# Analog_-_High_Speed_SE.net
KiCad netlist of a schematic drawn in Altium Designer
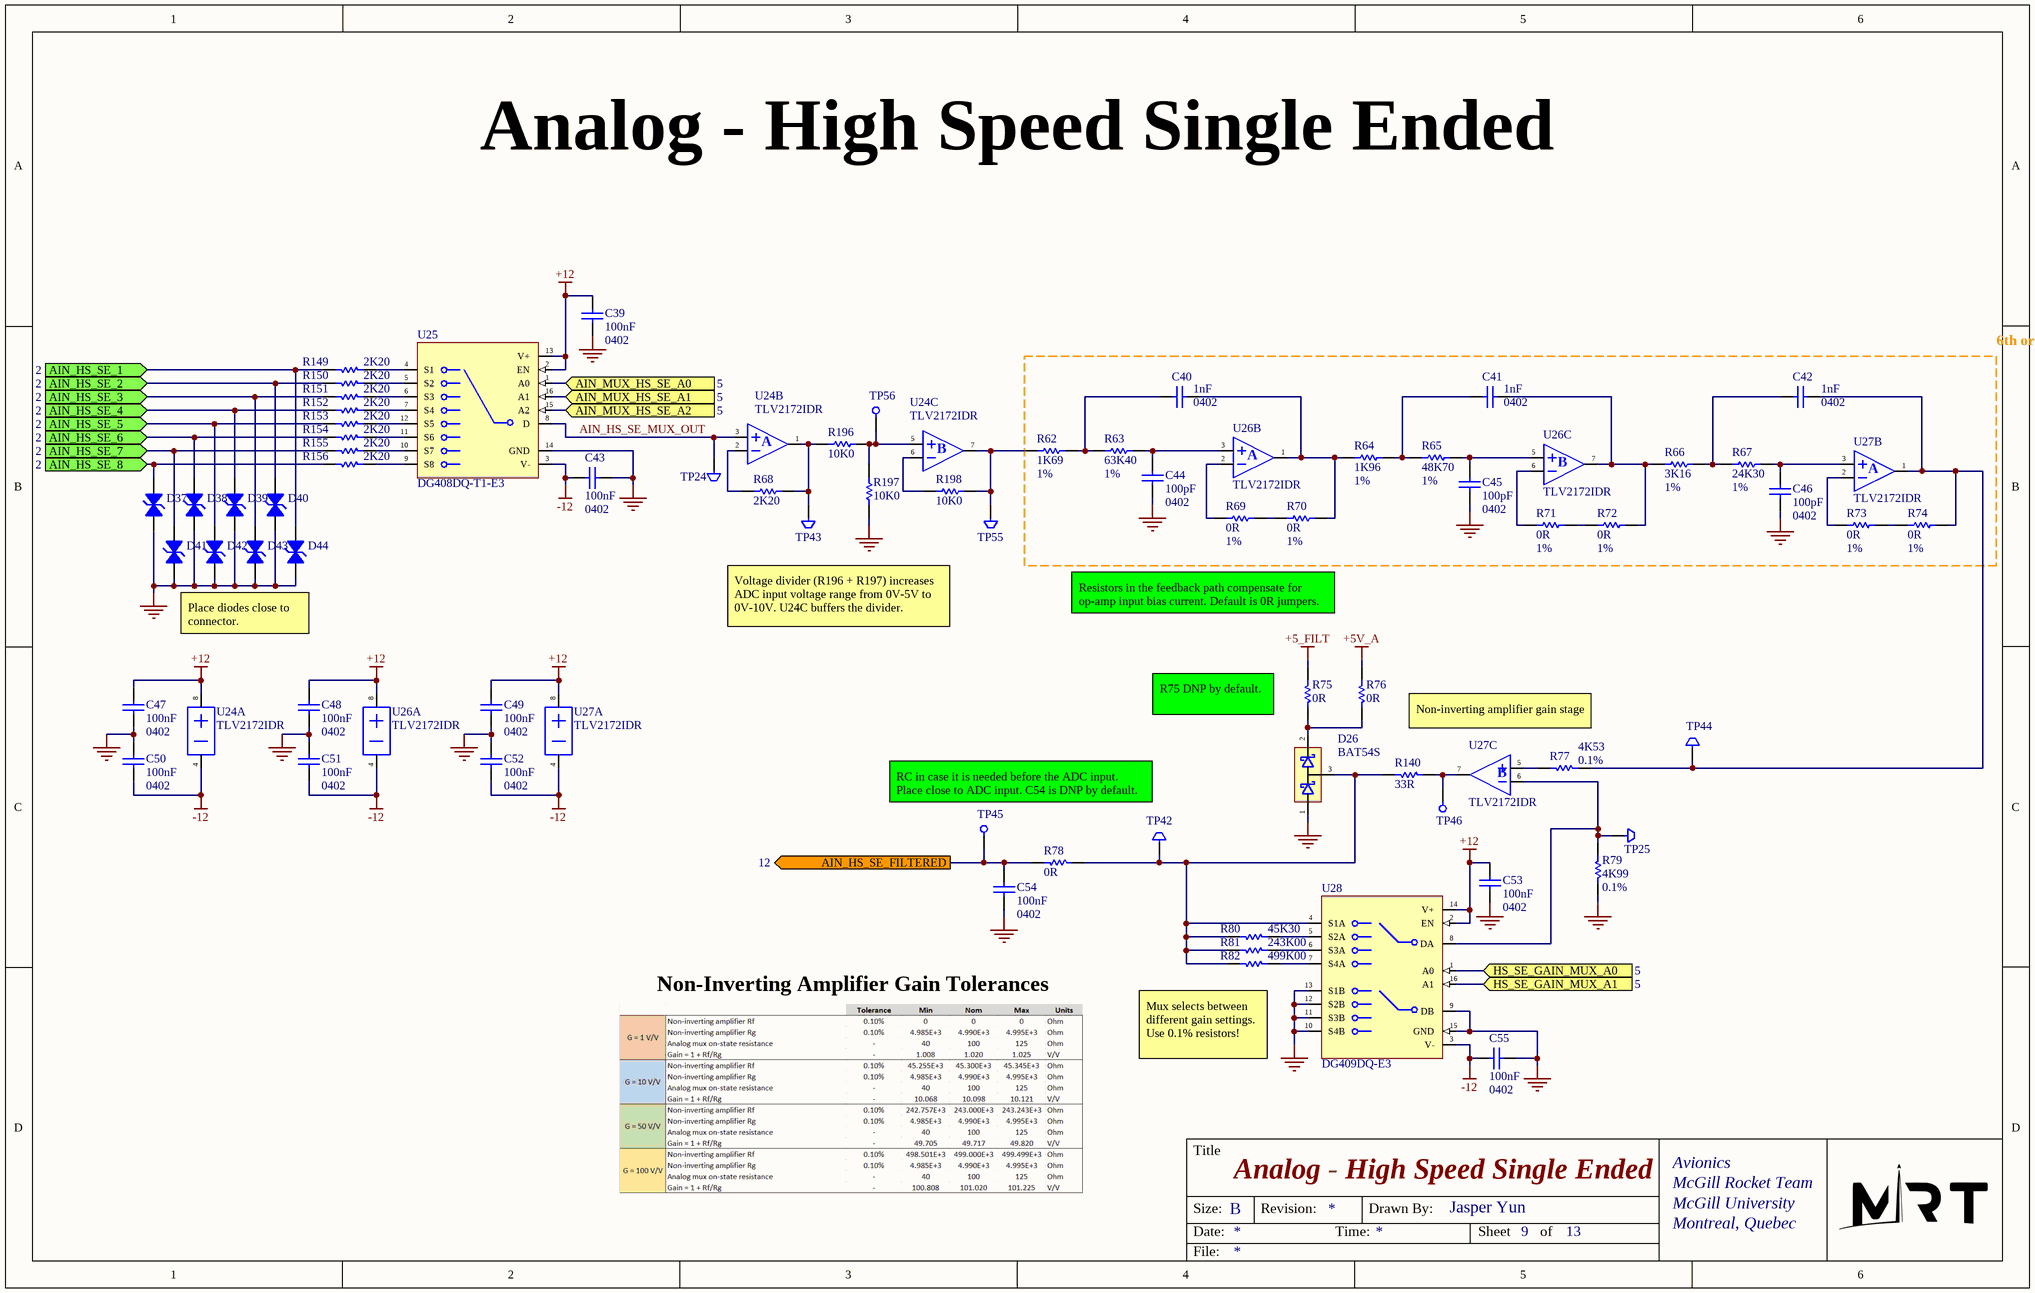
[diagram p0: Analog - High Speed SE.SchDoc]

(export (version "E")
  (design (tool "Eeschema 10.0.6"))
  (components
    (comp (ref "C39")
      (value "100nF")
      (footprint "0402 CAP")
      (description "Capacitor")
      (fields (field (name "ALTIUM_VALUE") "0402") (field (name "PUBLISHER") "Altium Limited"))
      (libsource (lib "Miscellaneous Devices") (part "Cap"))
    )
    (comp (ref "C40")
      (value "1nF")
      (footprint "0402 CAP")
      (description "Capacitor")
      (fields (field (name "ALTIUM_VALUE") "0402") (field (name "PUBLISHER") "Altium Limited"))
      (libsource (lib "Miscellaneous Devices") (part "Cap"))
    )
    (comp (ref "C41")
      (value "1nF")
      (footprint "0402 CAP")
      (description "Capacitor")
      (fields (field (name "ALTIUM_VALUE") "0402") (field (name "PUBLISHER") "Altium Limited"))
      (libsource (lib "Miscellaneous Devices") (part "Cap"))
    )
    (comp (ref "C42")
      (value "1nF")
      (footprint "0402 CAP")
      (description "Capacitor")
      (fields (field (name "ALTIUM_VALUE") "0402") (field (name "PUBLISHER") "Altium Limited"))
      (libsource (lib "Miscellaneous Devices") (part "Cap"))
    )
    (comp (ref "C43")
      (value "100nF")
      (footprint "0402 CAP")
      (description "Capacitor")
      (fields (field (name "ALTIUM_VALUE") "0402") (field (name "PUBLISHER") "Altium Limited"))
      (libsource (lib "Miscellaneous Devices") (part "Cap"))
    )
    (comp (ref "C44")
      (value "100pF")
      (footprint "0402 CAP")
      (description "Capacitor")
      (fields (field (name "ALTIUM_VALUE") "0402") (field (name "PUBLISHER") "Altium Limited"))
      (libsource (lib "Miscellaneous Devices") (part "Cap"))
    )
    (comp (ref "C45")
      (value "100pF")
      (footprint "0402 CAP")
      (description "Capacitor")
      (fields (field (name "ALTIUM_VALUE") "0402") (field (name "PUBLISHER") "Altium Limited"))
      (libsource (lib "Miscellaneous Devices") (part "Cap"))
    )
    (comp (ref "C46")
      (value "100pF")
      (footprint "0402 CAP")
      (description "Capacitor")
      (fields (field (name "ALTIUM_VALUE") "0402") (field (name "PUBLISHER") "Altium Limited"))
      (libsource (lib "Miscellaneous Devices") (part "Cap"))
    )
    (comp (ref "C47")
      (value "100nF")
      (footprint "0402 CAP")
      (description "Capacitor")
      (fields (field (name "ALTIUM_VALUE") "0402") (field (name "PUBLISHER") "Altium Limited"))
      (libsource (lib "Miscellaneous Devices") (part "Cap"))
    )
    (comp (ref "C48")
      (value "100nF")
      (footprint "0402 CAP")
      (description "Capacitor")
      (fields (field (name "ALTIUM_VALUE") "0402") (field (name "PUBLISHER") "Altium Limited"))
      (libsource (lib "Miscellaneous Devices") (part "Cap"))
    )
    (comp (ref "C49")
      (value "100nF")
      (footprint "0402 CAP")
      (description "Capacitor")
      (fields (field (name "ALTIUM_VALUE") "0402") (field (name "PUBLISHER") "Altium Limited"))
      (libsource (lib "Miscellaneous Devices") (part "Cap"))
    )
    (comp (ref "C50")
      (value "100nF")
      (footprint "0402 CAP")
      (description "Capacitor")
      (fields (field (name "ALTIUM_VALUE") "0402") (field (name "PUBLISHER") "Altium Limited"))
      (libsource (lib "Miscellaneous Devices") (part "Cap"))
    )
    (comp (ref "C51")
      (value "100nF")
      (footprint "0402 CAP")
      (description "Capacitor")
      (fields (field (name "ALTIUM_VALUE") "0402") (field (name "PUBLISHER") "Altium Limited"))
      (libsource (lib "Miscellaneous Devices") (part "Cap"))
    )
    (comp (ref "C52")
      (value "100nF")
      (footprint "0402 CAP")
      (description "Capacitor")
      (fields (field (name "ALTIUM_VALUE") "0402") (field (name "PUBLISHER") "Altium Limited"))
      (libsource (lib "Miscellaneous Devices") (part "Cap"))
    )
    (comp (ref "C53")
      (value "100nF")
      (footprint "0402 CAP")
      (description "Capacitor")
      (fields (field (name "ALTIUM_VALUE") "0402") (field (name "PUBLISHER") "Altium Limited"))
      (libsource (lib "Miscellaneous Devices") (part "Cap"))
    )
    (comp (ref "C54")
      (value "100nF")
      (footprint "0402 CAP")
      (description "Capacitor")
      (fields (field (name "ALTIUM_VALUE") "0402") (field (name "PUBLISHER") "Altium Limited"))
      (libsource (lib "Miscellaneous Devices") (part "Cap"))
    )
    (comp (ref "C55")
      (value "100nF")
      (footprint "0402 CAP")
      (description "Capacitor")
      (fields (field (name "ALTIUM_VALUE") "0402") (field (name "PUBLISHER") "Altium Limited"))
      (libsource (lib "Miscellaneous Devices") (part "Cap"))
    )
    (comp (ref "D26")
      (value "BAT54S")
      (footprint "SOT23-3")
      (description "Rectifier Diode Small Signal Schottky 40V 0.3A 5ns 3-Pin SOT-23 T/R")
      (fields
        (field (name "MANUFACTURER") "STMicroelectronics")
        (field (name "MANUFACTURER PART NUMBER") "BAT54SFILM")
      )
      (libsource (lib "MRT SCH Library") (part "Schottky Diode Array BAT54S"))
    )
    (comp (ref "D37")
      (value "D12V0L1B2LP-7B")
      (footprint "DFN1006-2")
      (description "Bidirectional Zener diode")
      (libsource (lib "MRT SCH Library") (part "Diode Zener Bidirectional"))
    )
    (comp (ref "D38")
      (value "D12V0L1B2LP-7B")
      (footprint "DFN1006-2")
      (description "Bidirectional Zener diode")
      (libsource (lib "MRT SCH Library") (part "Diode Zener Bidirectional"))
    )
    (comp (ref "D39")
      (value "D12V0L1B2LP-7B")
      (footprint "DFN1006-2")
      (description "Bidirectional Zener diode")
      (libsource (lib "MRT SCH Library") (part "Diode Zener Bidirectional"))
    )
    (comp (ref "D40")
      (value "D12V0L1B2LP-7B")
      (footprint "DFN1006-2")
      (description "Bidirectional Zener diode")
      (libsource (lib "MRT SCH Library") (part "Diode Zener Bidirectional"))
    )
    (comp (ref "D41")
      (value "D12V0L1B2LP-7B")
      (footprint "DFN1006-2")
      (description "Bidirectional Zener diode")
      (libsource (lib "MRT SCH Library") (part "Diode Zener Bidirectional"))
    )
    (comp (ref "D42")
      (value "D12V0L1B2LP-7B")
      (footprint "DFN1006-2")
      (description "Bidirectional Zener diode")
      (libsource (lib "MRT SCH Library") (part "Diode Zener Bidirectional"))
    )
    (comp (ref "D43")
      (value "D12V0L1B2LP-7B")
      (footprint "DFN1006-2")
      (description "Bidirectional Zener diode")
      (libsource (lib "MRT SCH Library") (part "Diode Zener Bidirectional"))
    )
    (comp (ref "D44")
      (value "D12V0L1B2LP-7B")
      (footprint "DFN1006-2")
      (description "Bidirectional Zener diode")
      (libsource (lib "MRT SCH Library") (part "Diode Zener Bidirectional"))
    )
    (comp (ref "R62")
      (value "1K69")
      (footprint "0402 RES")
      (description "Resistor")
      (fields (field (name "ALTIUM_VALUE") "1%") (field (name "PUBLISHER") "Altium Limited"))
      (libsource (lib "Miscellaneous Devices") (part "Res1"))
    )
    (comp (ref "R63")
      (value "63K40")
      (footprint "0402 RES")
      (description "Resistor")
      (fields (field (name "ALTIUM_VALUE") "1%") (field (name "PUBLISHER") "Altium Limited"))
      (libsource (lib "Miscellaneous Devices") (part "Res1"))
    )
    (comp (ref "R64")
      (value "1K96")
      (footprint "0402 RES")
      (description "Resistor")
      (fields (field (name "ALTIUM_VALUE") "1%") (field (name "PUBLISHER") "Altium Limited"))
      (libsource (lib "Miscellaneous Devices") (part "Res1"))
    )
    (comp (ref "R65")
      (value "48K70")
      (footprint "0402 RES")
      (description "Resistor")
      (fields (field (name "ALTIUM_VALUE") "1%") (field (name "PUBLISHER") "Altium Limited"))
      (libsource (lib "Miscellaneous Devices") (part "Res1"))
    )
    (comp (ref "R66")
      (value "3K16")
      (footprint "0402 RES")
      (description "Resistor")
      (fields (field (name "ALTIUM_VALUE") "1%") (field (name "PUBLISHER") "Altium Limited"))
      (libsource (lib "Miscellaneous Devices") (part "Res1"))
    )
    (comp (ref "R67")
      (value "24K30")
      (footprint "0402 RES")
      (description "Resistor")
      (fields (field (name "ALTIUM_VALUE") "1%") (field (name "PUBLISHER") "Altium Limited"))
      (libsource (lib "Miscellaneous Devices") (part "Res1"))
    )
    (comp (ref "R68")
      (value "2K20")
      (footprint "0402 RES")
      (description "Resistor")
      (fields (field (name "PUBLISHER") "Altium Limited"))
      (libsource (lib "Miscellaneous Devices") (part "Res1"))
    )
    (comp (ref "R69")
      (value "0R")
      (footprint "0402 RES")
      (description "Resistor")
      (fields (field (name "ALTIUM_VALUE") "1%") (field (name "PUBLISHER") "Altium Limited"))
      (libsource (lib "Miscellaneous Devices") (part "Res1"))
    )
    (comp (ref "R70")
      (value "0R")
      (footprint "0402 RES")
      (description "Resistor")
      (fields (field (name "ALTIUM_VALUE") "1%") (field (name "PUBLISHER") "Altium Limited"))
      (libsource (lib "Miscellaneous Devices") (part "Res1"))
    )
    (comp (ref "R71")
      (value "0R")
      (footprint "0402 RES")
      (description "Resistor")
      (fields (field (name "ALTIUM_VALUE") "1%") (field (name "PUBLISHER") "Altium Limited"))
      (libsource (lib "Miscellaneous Devices") (part "Res1"))
    )
    (comp (ref "R72")
      (value "0R")
      (footprint "0402 RES")
      (description "Resistor")
      (fields (field (name "ALTIUM_VALUE") "1%") (field (name "PUBLISHER") "Altium Limited"))
      (libsource (lib "Miscellaneous Devices") (part "Res1"))
    )
    (comp (ref "R73")
      (value "0R")
      (footprint "0402 RES")
      (description "Resistor")
      (fields (field (name "ALTIUM_VALUE") "1%") (field (name "PUBLISHER") "Altium Limited"))
      (libsource (lib "Miscellaneous Devices") (part "Res1"))
    )
    (comp (ref "R74")
      (value "0R")
      (footprint "0402 RES")
      (description "Resistor")
      (fields (field (name "ALTIUM_VALUE") "1%") (field (name "PUBLISHER") "Altium Limited"))
      (libsource (lib "Miscellaneous Devices") (part "Res1"))
    )
    (comp (ref "R75")
      (value "0R")
      (footprint "0402 RES")
      (description "Resistor")
      (fields (field (name "PUBLISHER") "Altium Limited"))
      (libsource (lib "Miscellaneous Devices") (part "Res1"))
    )
    (comp (ref "R76")
      (value "0R")
      (footprint "0402 RES")
      (description "Resistor")
      (fields (field (name "PUBLISHER") "Altium Limited"))
      (libsource (lib "Miscellaneous Devices") (part "Res1"))
    )
    (comp (ref "R77")
      (value "4K53")
      (footprint "0402 RES")
      (description "Resistor")
      (fields (field (name "ALTIUM_VALUE") "0.1%") (field (name "PUBLISHER") "Altium Limited"))
      (libsource (lib "Miscellaneous Devices") (part "Res1"))
    )
    (comp (ref "R78")
      (value "0R")
      (footprint "0402 RES")
      (description "Resistor")
      (fields (field (name "PUBLISHER") "Altium Limited"))
      (libsource (lib "Miscellaneous Devices") (part "Res1"))
    )
    (comp (ref "R79")
      (value "4K99")
      (footprint "0402 RES")
      (description "Resistor")
      (fields (field (name "ALTIUM_VALUE") "0.1%") (field (name "PUBLISHER") "Altium Limited"))
      (libsource (lib "Miscellaneous Devices") (part "Res1"))
    )
    (comp (ref "R80")
      (value "45K30")
      (footprint "0402 RES")
      (description "Resistor")
      (fields (field (name "PUBLISHER") "Altium Limited"))
      (libsource (lib "Miscellaneous Devices") (part "Res1"))
    )
    (comp (ref "R81")
      (value "243K00")
      (footprint "0402 RES")
      (description "Resistor")
      (fields (field (name "PUBLISHER") "Altium Limited"))
      (libsource (lib "Miscellaneous Devices") (part "Res1"))
    )
    (comp (ref "R82")
      (value "499K00")
      (footprint "0402 RES")
      (description "Resistor")
      (fields (field (name "PUBLISHER") "Altium Limited"))
      (libsource (lib "Miscellaneous Devices") (part "Res1"))
    )
    (comp (ref "R140")
      (value "33R")
      (footprint "0402 RES")
      (description "Resistor")
      (fields (field (name "PUBLISHER") "Altium Limited"))
      (libsource (lib "Miscellaneous Devices") (part "Res1"))
    )
    (comp (ref "R149")
      (value "2K20")
      (footprint "0402 RES")
      (description "Resistor")
      (fields (field (name "PUBLISHER") "Altium Limited"))
      (libsource (lib "Miscellaneous Devices") (part "Res1"))
    )
    (comp (ref "R150")
      (value "2K20")
      (footprint "0402 RES")
      (description "Resistor")
      (fields (field (name "PUBLISHER") "Altium Limited"))
      (libsource (lib "Miscellaneous Devices") (part "Res1"))
    )
    (comp (ref "R151")
      (value "2K20")
      (footprint "0402 RES")
      (description "Resistor")
      (fields (field (name "PUBLISHER") "Altium Limited"))
      (libsource (lib "Miscellaneous Devices") (part "Res1"))
    )
    (comp (ref "R152")
      (value "2K20")
      (footprint "0402 RES")
      (description "Resistor")
      (fields (field (name "PUBLISHER") "Altium Limited"))
      (libsource (lib "Miscellaneous Devices") (part "Res1"))
    )
    (comp (ref "R153")
      (value "2K20")
      (footprint "0402 RES")
      (description "Resistor")
      (fields (field (name "PUBLISHER") "Altium Limited"))
      (libsource (lib "Miscellaneous Devices") (part "Res1"))
    )
    (comp (ref "R154")
      (value "2K20")
      (footprint "0402 RES")
      (description "Resistor")
      (fields (field (name "PUBLISHER") "Altium Limited"))
      (libsource (lib "Miscellaneous Devices") (part "Res1"))
    )
    (comp (ref "R155")
      (value "2K20")
      (footprint "0402 RES")
      (description "Resistor")
      (fields (field (name "PUBLISHER") "Altium Limited"))
      (libsource (lib "Miscellaneous Devices") (part "Res1"))
    )
    (comp (ref "R156")
      (value "2K20")
      (footprint "0402 RES")
      (description "Resistor")
      (fields (field (name "PUBLISHER") "Altium Limited"))
      (libsource (lib "Miscellaneous Devices") (part "Res1"))
    )
    (comp (ref "R196")
      (value "10K0")
      (footprint "0402 RES")
      (description "Resistor")
      (fields (field (name "PUBLISHER") "Altium Limited"))
      (libsource (lib "Miscellaneous Devices") (part "Res1"))
    )
    (comp (ref "R197")
      (value "10K0")
      (footprint "0402 RES")
      (description "Resistor")
      (fields (field (name "PUBLISHER") "Altium Limited"))
      (libsource (lib "Miscellaneous Devices") (part "Res1"))
    )
    (comp (ref "R198")
      (value "10K0")
      (footprint "0402 RES")
      (description "Resistor")
      (fields (field (name "PUBLISHER") "Altium Limited"))
      (libsource (lib "Miscellaneous Devices") (part "Res1"))
    )
    (comp (ref "TP24")
      (value "Test Point - Keystone 5015")
      (footprint "Test Point Keystone 5015")
      (description "Keystone 5015 Test point")
      (libsource (lib "MRT SCH Library") (part "Test Point - Keystone 5015"))
    )
    (comp (ref "TP25")
      (value "Test Point - Keystone 5015")
      (footprint "Test Point Keystone 5015")
      (description "Keystone 5015 Test point")
      (libsource (lib "MRT SCH Library") (part "Test Point - Keystone 5015"))
    )
    (comp (ref "TP42")
      (value "Test Point - Keystone 5015")
      (footprint "Test Point Keystone 5015")
      (description "Keystone 5015 Test point")
      (libsource (lib "MRT SCH Library") (part "Test Point - Keystone 5015"))
    )
    (comp (ref "TP43")
      (value "Test Point - Keystone 5015")
      (footprint "Test Point Keystone 5015")
      (description "Keystone 5015 Test point")
      (libsource (lib "MRT SCH Library") (part "Test Point - Keystone 5015"))
    )
    (comp (ref "TP44")
      (value "Test Point - Keystone 5015")
      (footprint "Test Point Keystone 5015")
      (description "Keystone 5015 Test point")
      (libsource (lib "MRT SCH Library") (part "Test Point - Keystone 5015"))
    )
    (comp (ref "TP45")
      (value "Test Point - SMD Pad")
      (footprint "TEST POINT SMD PAD")
      (description "SMD Pad test point")
      (libsource (lib "MRT SCH Library") (part "Test Point - SMD Pad"))
    )
    (comp (ref "TP46")
      (value "Test Point - SMD Pad")
      (footprint "TEST POINT SMD PAD")
      (description "SMD Pad test point")
      (libsource (lib "MRT SCH Library") (part "Test Point - SMD Pad"))
    )
    (comp (ref "TP55")
      (value "Test Point - Keystone 5015")
      (footprint "Test Point Keystone 5015")
      (description "Keystone 5015 Test point")
      (libsource (lib "MRT SCH Library") (part "Test Point - Keystone 5015"))
    )
    (comp (ref "TP56")
      (value "Test Point - SMD Pad")
      (footprint "TEST POINT SMD PAD")
      (description "SMD Pad test point")
      (libsource (lib "MRT SCH Library") (part "Test Point - SMD Pad"))
    )
    (comp (ref "U24")
      (value "TLV2172IDR")
      (footprint "SOIC-8")
      (fields
        (field (name "MANUFACTURER") "Texas Instruments")
        (field (name "MANUFACTURER PART NUMBER") "RC4580IDR")
      )
      (libsource (lib "MRT SCH Library") (part "OP AMP RC4580"))
    )
    (comp (ref "U25")
      (value "DG408DQ-T1-E3")
      (footprint "TSSOP-16")
      (description "DG408DQ-T1-E3; Multiplexer Single 8: 1; 15 V; 18 V; 24 V; 28 V; 16-Pin TSSOP")
      (fields (field (name "MANUFACTURER") "Vishay Siliconix"))
      (libsource (lib "MRT SCH Library") (part "Analog Mux DG408DQ-T1-E3"))
    )
    (comp (ref "U26")
      (value "TLV2172IDR")
      (footprint "SOIC-8")
      (fields
        (field (name "MANUFACTURER") "Texas Instruments")
        (field (name "MANUFACTURER PART NUMBER") "RC4580IDR")
      )
      (libsource (lib "MRT SCH Library") (part "OP AMP RC4580"))
    )
    (comp (ref "U27")
      (value "TLV2172IDR")
      (footprint "SOIC-8")
      (fields
        (field (name "MANUFACTURER") "Texas Instruments")
        (field (name "MANUFACTURER PART NUMBER") "RC4580IDR")
      )
      (libsource (lib "MRT SCH Library") (part "OP AMP RC4580"))
    )
    (comp (ref "U28")
      (value "DG409DQ-E3")
      (footprint "TSSOP-16")
      (description "DG409 Series 20 V 8-Ch/Dual 4-Ch High-Performance CMOS Analog Multiplexer")
      (fields (field (name "MANUFACTURER") "Vishay Siliconix"))
      (libsource (lib "MRT SCH Library") (part "Analog Mux DG409DQ-E3"))
    )
  )
  (nets
    (net (code "1") (name "+5V_A") (class "Default")
      (node (ref "R76") (pin "1") (pinfunction "1_1") (pintype "passive"))
    )
    (net (code "2") (name "+5_FILT") (class "Default")
      (node (ref "R75") (pin "1") (pinfunction "1_1") (pintype "passive"))
    )
    (net (code "3") (name "+12") (class "Default")
      (node (ref "C39") (pin "2") (pinfunction "2_2") (pintype "passive"))
      (node (ref "C47") (pin "2") (pinfunction "2_2") (pintype "passive"))
      (node (ref "C48") (pin "2") (pinfunction "2_2") (pintype "passive"))
      (node (ref "C49") (pin "2") (pinfunction "2_2") (pintype "passive"))
      (node (ref "C53") (pin "2") (pinfunction "2_2") (pintype "passive"))
      (node (ref "U24") (pin "8") (pinfunction "VCC+_8") (pintype "passive"))
      (node (ref "U25") (pin "13") (pinfunction "V+_13") (pintype "passive"))
      (node (ref "U25") (pin "2") (pinfunction "EN_2") (pintype "input"))
      (node (ref "U26") (pin "8") (pinfunction "VCC+_8") (pintype "passive"))
      (node (ref "U27") (pin "8") (pinfunction "VCC+_8") (pintype "passive"))
      (node (ref "U28") (pin "14") (pinfunction "V+_14") (pintype "passive"))
      (node (ref "U28") (pin "2") (pinfunction "EN_2") (pintype "input"))
    )
    (net (code "4") (name "-12") (class "Default")
      (node (ref "C43") (pin "2") (pinfunction "2_2") (pintype "passive"))
      (node (ref "C50") (pin "1") (pinfunction "1_1") (pintype "passive"))
      (node (ref "C51") (pin "1") (pinfunction "1_1") (pintype "passive"))
      (node (ref "C52") (pin "1") (pinfunction "1_1") (pintype "passive"))
      (node (ref "C55") (pin "2") (pinfunction "2_2") (pintype "passive"))
      (node (ref "U24") (pin "4") (pinfunction "VCC-_4") (pintype "passive"))
      (node (ref "U25") (pin "3") (pinfunction "V-_3") (pintype "passive"))
      (node (ref "U26") (pin "4") (pinfunction "VCC-_4") (pintype "passive"))
      (node (ref "U27") (pin "4") (pinfunction "VCC-_4") (pintype "passive"))
      (node (ref "U28") (pin "3") (pinfunction "V-_3") (pintype "passive"))
    )
    (net (code "5") (name "/AIN_HS_SE_1") (class "Default")
      (node (ref "D44") (pin "2") (pinfunction "2_2") (pintype "passive"))
      (node (ref "R149") (pin "1") (pinfunction "1_1") (pintype "passive"))
    )
    (net (code "6") (name "/AIN_HS_SE_2") (class "Default")
      (node (ref "D40") (pin "2") (pinfunction "2_2") (pintype "passive"))
      (node (ref "R150") (pin "1") (pinfunction "1_1") (pintype "passive"))
    )
    (net (code "7") (name "/AIN_HS_SE_3") (class "Default")
      (node (ref "D43") (pin "2") (pinfunction "2_2") (pintype "passive"))
      (node (ref "R151") (pin "1") (pinfunction "1_1") (pintype "passive"))
    )
    (net (code "8") (name "/AIN_HS_SE_4") (class "Default")
      (node (ref "D39") (pin "2") (pinfunction "2_2") (pintype "passive"))
      (node (ref "R152") (pin "1") (pinfunction "1_1") (pintype "passive"))
    )
    (net (code "9") (name "/AIN_HS_SE_5") (class "Default")
      (node (ref "D42") (pin "2") (pinfunction "2_2") (pintype "passive"))
      (node (ref "R153") (pin "1") (pinfunction "1_1") (pintype "passive"))
    )
    (net (code "10") (name "/AIN_HS_SE_6") (class "Default")
      (node (ref "D38") (pin "2") (pinfunction "2_2") (pintype "passive"))
      (node (ref "R154") (pin "1") (pinfunction "1_1") (pintype "passive"))
    )
    (net (code "11") (name "/AIN_HS_SE_7") (class "Default")
      (node (ref "D41") (pin "2") (pinfunction "2_2") (pintype "passive"))
      (node (ref "R155") (pin "1") (pinfunction "1_1") (pintype "passive"))
    )
    (net (code "12") (name "/AIN_HS_SE_8") (class "Default")
      (node (ref "D37") (pin "2") (pinfunction "2_2") (pintype "passive"))
      (node (ref "R156") (pin "1") (pinfunction "1_1") (pintype "passive"))
    )
    (net (code "13") (name "/AIN_HS_SE_FILTERED") (class "Default")
      (node (ref "C54") (pin "2") (pinfunction "2_2") (pintype "passive"))
      (node (ref "R78") (pin "1") (pinfunction "1_1") (pintype "passive"))
      (node (ref "TP45") (pin "1") (pinfunction "1_1") (pintype "passive"))
    )
    (net (code "14") (name "/AIN_HS_SE_MUX_OUT") (class "Default")
      (node (ref "TP24") (pin "1") (pinfunction "1_1") (pintype "passive"))
      (node (ref "U24") (pin "3") (pinfunction "3_3") (pintype "passive"))
      (node (ref "U25") (pin "8") (pinfunction "D_8") (pintype "passive"))
    )
    (net (code "15") (name "/AIN_MUX_HS_SE_A0") (class "Default")
      (node (ref "U25") (pin "1") (pinfunction "A0_1") (pintype "input"))
    )
    (net (code "16") (name "/AIN_MUX_HS_SE_A1") (class "Default")
      (node (ref "U25") (pin "16") (pinfunction "A1_16") (pintype "input"))
    )
    (net (code "17") (name "/AIN_MUX_HS_SE_A2") (class "Default")
      (node (ref "U25") (pin "15") (pinfunction "A2_15") (pintype "input"))
    )
    (net (code "18") (name "/HS_SE_GAIN_MUX_A0") (class "Default")
      (node (ref "U28") (pin "1") (pinfunction "A0_1") (pintype "input"))
    )
    (net (code "19") (name "/HS_SE_GAIN_MUX_A1") (class "Default")
      (node (ref "U28") (pin "16") (pinfunction "A1_16") (pintype "input"))
    )
    (net (code "20") (name "GND") (class "Default")
      (node (ref "C39") (pin "1") (pinfunction "1_1") (pintype "passive"))
      (node (ref "C43") (pin "1") (pinfunction "1_1") (pintype "passive"))
      (node (ref "C44") (pin "1") (pinfunction "1_1") (pintype "passive"))
      (node (ref "C45") (pin "1") (pinfunction "1_1") (pintype "passive"))
      (node (ref "C46") (pin "1") (pinfunction "1_1") (pintype "passive"))
      (node (ref "C47") (pin "1") (pinfunction "1_1") (pintype "passive"))
      (node (ref "C48") (pin "1") (pinfunction "1_1") (pintype "passive"))
      (node (ref "C49") (pin "1") (pinfunction "1_1") (pintype "passive"))
      (node (ref "C50") (pin "2") (pinfunction "2_2") (pintype "passive"))
      (node (ref "C51") (pin "2") (pinfunction "2_2") (pintype "passive"))
      (node (ref "C52") (pin "2") (pinfunction "2_2") (pintype "passive"))
      (node (ref "C53") (pin "1") (pinfunction "1_1") (pintype "passive"))
      (node (ref "C54") (pin "1") (pinfunction "1_1") (pintype "passive"))
      (node (ref "C55") (pin "1") (pinfunction "1_1") (pintype "passive"))
      (node (ref "D26") (pin "1") (pinfunction "1_1") (pintype "passive"))
      (node (ref "D37") (pin "1") (pinfunction "1_1") (pintype "passive"))
      (node (ref "D38") (pin "1") (pinfunction "1_1") (pintype "passive"))
      (node (ref "D39") (pin "1") (pinfunction "1_1") (pintype "passive"))
      (node (ref "D40") (pin "1") (pinfunction "1_1") (pintype "passive"))
      (node (ref "D41") (pin "1") (pinfunction "1_1") (pintype "passive"))
      (node (ref "D42") (pin "1") (pinfunction "1_1") (pintype "passive"))
      (node (ref "D43") (pin "1") (pinfunction "1_1") (pintype "passive"))
      (node (ref "D44") (pin "1") (pinfunction "1_1") (pintype "passive"))
      (node (ref "R197") (pin "1") (pinfunction "1_1") (pintype "passive"))
      (node (ref "R79") (pin "1") (pinfunction "1_1") (pintype "passive"))
      (node (ref "U25") (pin "14") (pinfunction "GND_14") (pintype "passive"))
      (node (ref "U28") (pin "10") (pinfunction "S4B_10") (pintype "passive"))
      (node (ref "U28") (pin "11") (pinfunction "S3B_11") (pintype "passive"))
      (node (ref "U28") (pin "12") (pinfunction "S2B_12") (pintype "passive"))
      (node (ref "U28") (pin "13") (pinfunction "S1B_13") (pintype "passive"))
      (node (ref "U28") (pin "15") (pinfunction "GND_15") (pintype "input"))
      (node (ref "U28") (pin "9") (pinfunction "DB_9") (pintype "passive"))
    )
    (net (code "21") (name "Net-(C40-Pad1)") (class "Default")
      (node (ref "C40") (pin "1") (pinfunction "1_1") (pintype "passive"))
      (node (ref "R64") (pin "1") (pinfunction "1_1") (pintype "passive"))
      (node (ref "R70") (pin "2") (pinfunction "2_2") (pintype "passive"))
      (node (ref "U26") (pin "1") (pinfunction "1_1") (pintype "passive"))
    )
    (net (code "22") (name "Net-(C40-Pad2)") (class "Default")
      (node (ref "C40") (pin "2") (pinfunction "2_2") (pintype "passive"))
      (node (ref "R62") (pin "2") (pinfunction "2_2") (pintype "passive"))
      (node (ref "R63") (pin "1") (pinfunction "1_1") (pintype "passive"))
    )
    (net (code "23") (name "Net-(C41-Pad1)") (class "Default")
      (node (ref "C41") (pin "1") (pinfunction "1_1") (pintype "passive"))
      (node (ref "R66") (pin "1") (pinfunction "1_1") (pintype "passive"))
      (node (ref "R72") (pin "2") (pinfunction "2_2") (pintype "passive"))
      (node (ref "U26") (pin "7") (pinfunction "7_7") (pintype "passive"))
    )
    (net (code "24") (name "Net-(C41-Pad2)") (class "Default")
      (node (ref "C41") (pin "2") (pinfunction "2_2") (pintype "passive"))
      (node (ref "R64") (pin "2") (pinfunction "2_2") (pintype "passive"))
      (node (ref "R65") (pin "1") (pinfunction "1_1") (pintype "passive"))
    )
    (net (code "25") (name "Net-(C42-Pad1)") (class "Default")
      (node (ref "C42") (pin "1") (pinfunction "1_1") (pintype "passive"))
      (node (ref "R74") (pin "2") (pinfunction "2_2") (pintype "passive"))
      (node (ref "R77") (pin "2") (pinfunction "2_2") (pintype "passive"))
      (node (ref "TP44") (pin "1") (pinfunction "1_1") (pintype "passive"))
      (node (ref "U27") (pin "1") (pinfunction "1_1") (pintype "passive"))
    )
    (net (code "26") (name "Net-(C42-Pad2)") (class "Default")
      (node (ref "C42") (pin "2") (pinfunction "2_2") (pintype "passive"))
      (node (ref "R66") (pin "2") (pinfunction "2_2") (pintype "passive"))
      (node (ref "R67") (pin "1") (pinfunction "1_1") (pintype "passive"))
    )
    (net (code "27") (name "Net-(C44-Pad2)") (class "Default")
      (node (ref "C44") (pin "2") (pinfunction "2_2") (pintype "passive"))
      (node (ref "R63") (pin "2") (pinfunction "2_2") (pintype "passive"))
      (node (ref "U26") (pin "3") (pinfunction "3_3") (pintype "passive"))
    )
    (net (code "28") (name "Net-(C45-Pad2)") (class "Default")
      (node (ref "C45") (pin "2") (pinfunction "2_2") (pintype "passive"))
      (node (ref "R65") (pin "2") (pinfunction "2_2") (pintype "passive"))
      (node (ref "U26") (pin "5") (pinfunction "5_5") (pintype "passive"))
    )
    (net (code "29") (name "Net-(C46-Pad2)") (class "Default")
      (node (ref "C46") (pin "2") (pinfunction "2_2") (pintype "passive"))
      (node (ref "R67") (pin "2") (pinfunction "2_2") (pintype "passive"))
      (node (ref "U27") (pin "3") (pinfunction "3_3") (pintype "passive"))
    )
    (net (code "30") (name "Net-(D26-Pad2)") (class "Default")
      (node (ref "D26") (pin "2") (pinfunction "2_2") (pintype "passive"))
      (node (ref "R75") (pin "2") (pinfunction "2_2") (pintype "passive"))
      (node (ref "R76") (pin "2") (pinfunction "2_2") (pintype "passive"))
    )
    (net (code "31") (name "Net-(R68-Pad1)") (class "Default")
      (node (ref "R68") (pin "1") (pinfunction "1_1") (pintype "passive"))
      (node (ref "U24") (pin "2") (pinfunction "2_2") (pintype "passive"))
    )
    (net (code "32") (name "Net-(R69-Pad1)") (class "Default")
      (node (ref "R69") (pin "1") (pinfunction "1_1") (pintype "passive"))
      (node (ref "U26") (pin "2") (pinfunction "2_2") (pintype "passive"))
    )
    (net (code "33") (name "Net-(R69-Pad2)") (class "Default")
      (node (ref "R69") (pin "2") (pinfunction "2_2") (pintype "passive"))
      (node (ref "R70") (pin "1") (pinfunction "1_1") (pintype "passive"))
    )
    (net (code "34") (name "Net-(R71-Pad1)") (class "Default")
      (node (ref "R71") (pin "1") (pinfunction "1_1") (pintype "passive"))
      (node (ref "U26") (pin "6") (pinfunction "6_6") (pintype "passive"))
    )
    (net (code "35") (name "Net-(R71-Pad2)") (class "Default")
      (node (ref "R71") (pin "2") (pinfunction "2_2") (pintype "passive"))
      (node (ref "R72") (pin "1") (pinfunction "1_1") (pintype "passive"))
    )
    (net (code "36") (name "Net-(R73-Pad1)") (class "Default")
      (node (ref "R73") (pin "1") (pinfunction "1_1") (pintype "passive"))
      (node (ref "U27") (pin "2") (pinfunction "2_2") (pintype "passive"))
    )
    (net (code "37") (name "Net-(R73-Pad2)") (class "Default")
      (node (ref "R73") (pin "2") (pinfunction "2_2") (pintype "passive"))
      (node (ref "R74") (pin "1") (pinfunction "1_1") (pintype "passive"))
    )
    (net (code "38") (name "Net-(R77-Pad1)") (class "Default")
      (node (ref "R77") (pin "1") (pinfunction "1_1") (pintype "passive"))
      (node (ref "U27") (pin "5") (pinfunction "5_5") (pintype "passive"))
    )
    (net (code "39") (name "Net-(R140-Pad2)") (class "Default")
      (node (ref "R140") (pin "2") (pinfunction "2_2") (pintype "passive"))
      (node (ref "TP46") (pin "1") (pinfunction "1_1") (pintype "passive"))
      (node (ref "U27") (pin "7") (pinfunction "7_7") (pintype "passive"))
    )
    (net (code "40") (name "Net-(R196-Pad1)") (class "Default")
      (node (ref "R196") (pin "1") (pinfunction "1_1") (pintype "passive"))
      (node (ref "R197") (pin "2") (pinfunction "2_2") (pintype "passive"))
      (node (ref "TP56") (pin "1") (pinfunction "1_1") (pintype "passive"))
      (node (ref "U24") (pin "5") (pinfunction "5_5") (pintype "passive"))
    )
    (net (code "41") (name "Net-(R196-Pad2)") (class "Default")
      (node (ref "R196") (pin "2") (pinfunction "2_2") (pintype "passive"))
      (node (ref "R68") (pin "2") (pinfunction "2_2") (pintype "passive"))
      (node (ref "TP43") (pin "1") (pinfunction "1_1") (pintype "passive"))
      (node (ref "U24") (pin "1") (pinfunction "1_1") (pintype "passive"))
    )
    (net (code "42") (name "Net-(R198-Pad1)") (class "Default")
      (node (ref "R198") (pin "1") (pinfunction "1_1") (pintype "passive"))
      (node (ref "R62") (pin "1") (pinfunction "1_1") (pintype "passive"))
      (node (ref "TP55") (pin "1") (pinfunction "1_1") (pintype "passive"))
      (node (ref "U24") (pin "7") (pinfunction "7_7") (pintype "passive"))
    )
    (net (code "43") (name "Net-(R198-Pad2)") (class "Default")
      (node (ref "R198") (pin "2") (pinfunction "2_2") (pintype "passive"))
      (node (ref "U24") (pin "6") (pinfunction "6_6") (pintype "passive"))
    )
    (net (code "44") (name "Net-(U25-S1)") (class "Default")
      (node (ref "R149") (pin "2") (pinfunction "2_2") (pintype "passive"))
      (node (ref "U25") (pin "4") (pinfunction "S1_4") (pintype "passive"))
    )
    (net (code "45") (name "Net-(U25-S2)") (class "Default")
      (node (ref "R150") (pin "2") (pinfunction "2_2") (pintype "passive"))
      (node (ref "U25") (pin "5") (pinfunction "S2_5") (pintype "passive"))
    )
    (net (code "46") (name "Net-(U25-S3)") (class "Default")
      (node (ref "R151") (pin "2") (pinfunction "2_2") (pintype "passive"))
      (node (ref "U25") (pin "6") (pinfunction "S3_6") (pintype "passive"))
    )
    (net (code "47") (name "Net-(U25-S4)") (class "Default")
      (node (ref "R152") (pin "2") (pinfunction "2_2") (pintype "passive"))
      (node (ref "U25") (pin "7") (pinfunction "S4_7") (pintype "passive"))
    )
    (net (code "48") (name "Net-(U25-S5)") (class "Default")
      (node (ref "R153") (pin "2") (pinfunction "2_2") (pintype "passive"))
      (node (ref "U25") (pin "12") (pinfunction "S5_12") (pintype "passive"))
    )
    (net (code "49") (name "Net-(U25-S6)") (class "Default")
      (node (ref "R154") (pin "2") (pinfunction "2_2") (pintype "passive"))
      (node (ref "U25") (pin "11") (pinfunction "S6_11") (pintype "passive"))
    )
    (net (code "50") (name "Net-(U25-S7)") (class "Default")
      (node (ref "R155") (pin "2") (pinfunction "2_2") (pintype "passive"))
      (node (ref "U25") (pin "10") (pinfunction "S7_10") (pintype "passive"))
    )
    (net (code "51") (name "Net-(U25-S8)") (class "Default")
      (node (ref "R156") (pin "2") (pinfunction "2_2") (pintype "passive"))
      (node (ref "U25") (pin "9") (pinfunction "S8_9") (pintype "passive"))
    )
    (net (code "52") (name "Net-(U28-DA)") (class "Default")
      (node (ref "R79") (pin "2") (pinfunction "2_2") (pintype "passive"))
      (node (ref "TP25") (pin "1") (pinfunction "1_1") (pintype "passive"))
      (node (ref "U27") (pin "6") (pinfunction "6_6") (pintype "passive"))
      (node (ref "U28") (pin "8") (pinfunction "DA_8") (pintype "passive"))
    )
    (net (code "53") (name "Net-(U28-S1A)") (class "Default")
      (node (ref "D26") (pin "3") (pinfunction "3_3") (pintype "passive"))
      (node (ref "R140") (pin "1") (pinfunction "1_1") (pintype "passive"))
      (node (ref "R78") (pin "2") (pinfunction "2_2") (pintype "passive"))
      (node (ref "R80") (pin "1") (pinfunction "1_1") (pintype "passive"))
      (node (ref "R81") (pin "1") (pinfunction "1_1") (pintype "passive"))
      (node (ref "R82") (pin "1") (pinfunction "1_1") (pintype "passive"))
      (node (ref "TP42") (pin "1") (pinfunction "1_1") (pintype "passive"))
      (node (ref "U28") (pin "4") (pinfunction "S1A_4") (pintype "passive"))
    )
    (net (code "54") (name "Net-(U28-S2A)") (class "Default")
      (node (ref "R80") (pin "2") (pinfunction "2_2") (pintype "passive"))
      (node (ref "U28") (pin "5") (pinfunction "S2A_5") (pintype "passive"))
    )
    (net (code "55") (name "Net-(U28-S3A)") (class "Default")
      (node (ref "R81") (pin "2") (pinfunction "2_2") (pintype "passive"))
      (node (ref "U28") (pin "6") (pinfunction "S3A_6") (pintype "passive"))
    )
    (net (code "56") (name "Net-(U28-S4A)") (class "Default")
      (node (ref "R82") (pin "2") (pinfunction "2_2") (pintype "passive"))
      (node (ref "U28") (pin "7") (pinfunction "S4A_7") (pintype "passive"))
    )
  )
)
